# SALO_CONTROLLER_PCB.net
KiCad netlist of a schematic drawn in Altium Designer
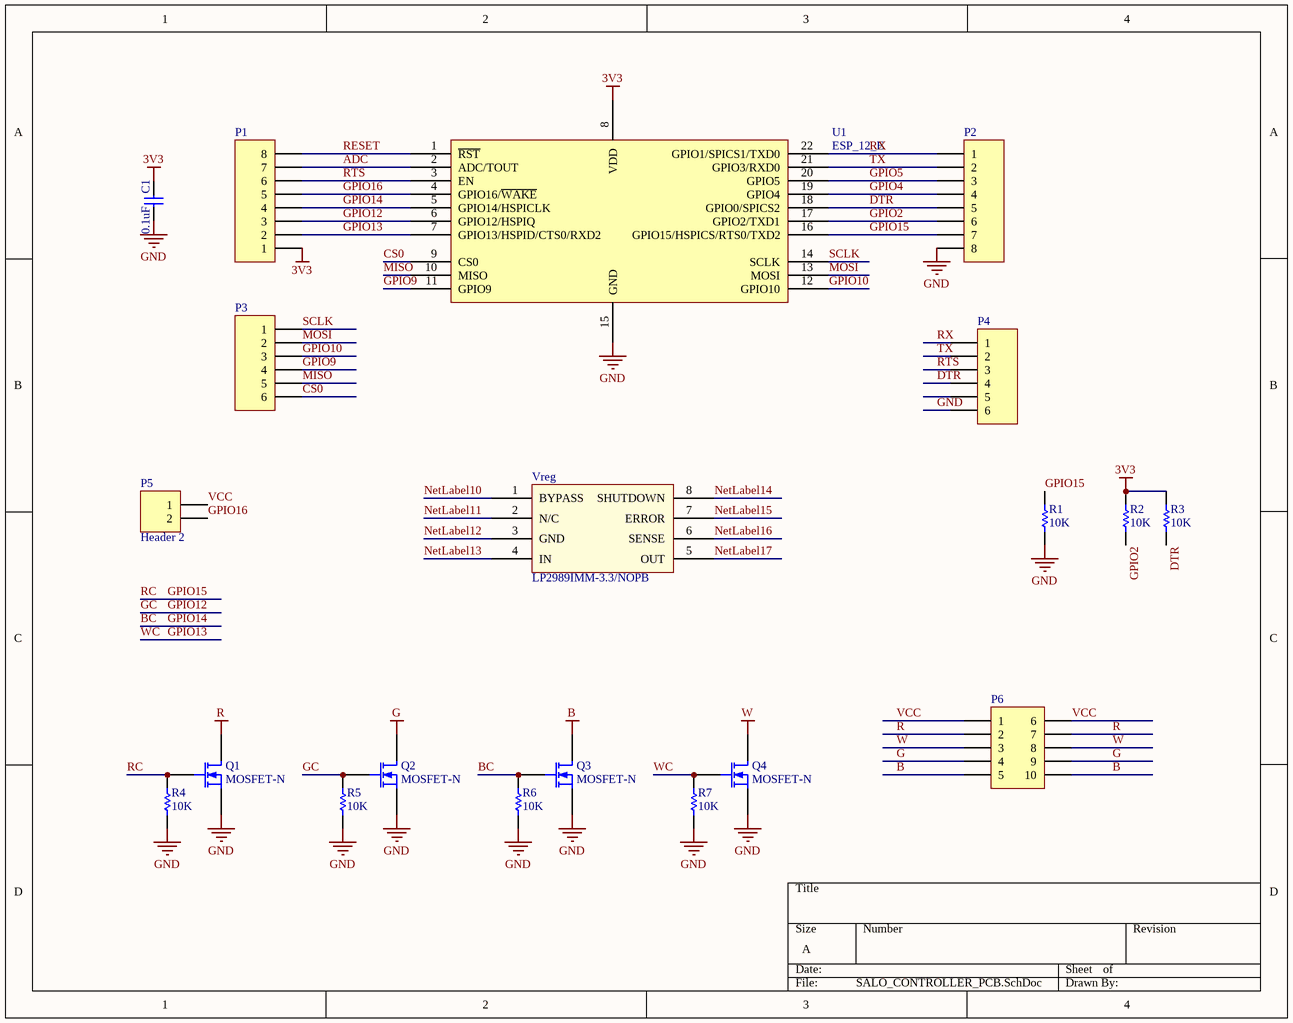
[diagram p0: SALO_CONTROLLER_PCB.SchDoc]

(export (version "E")
  (design (tool "Eeschema 10.0.6"))
  (components
    (comp (ref "C1")
      (value "0.1uF")
      (footprint "CAPC1608X06L")
      (description "Capacitor, X5R, ±10%")
      (fields (field (name "PART NUMBER") "C0603-4µ7") (field (name "PUBLISHER") "Nordic Semiconductor"))
      (libsource (lib "daniel_library") (part "CAP_0603"))
    )
    (comp (ref "P1")
      (value "Header 8")
      (footprint "HDR1X8")
      (description "Header, 8-Pin")
      (fields (field (name "PUBLISHER") "Altium Limited"))
      (libsource (lib "") (part "Header 8_1"))
    )
    (comp (ref "P2")
      (value "Header 8")
      (footprint "HDR1X8")
      (description "Header, 8-Pin")
      (fields (field (name "PUBLISHER") "Altium Limited"))
      (libsource (lib "Miscellaneous Connectors") (part "Header 8"))
    )
    (comp (ref "P3")
      (value "Header 6")
      (footprint "HDR1X6")
      (description "Header, 6-Pin")
      (fields (field (name "PUBLISHER") "Altium Limited"))
      (libsource (lib "") (part "Header 6_1"))
    )
    (comp (ref "P4")
      (value "Header 6")
      (footprint "HDR1X6")
      (description "Header, 6-Pin")
      (fields (field (name "PUBLISHER") "Altium Limited"))
      (libsource (lib "Miscellaneous Connectors") (part "Header 6"))
    )
    (comp (ref "P5")
      (value "Header 2")
      (footprint "HDR1X2")
      (description "Header, 2-Pin")
      (fields (field (name "PUBLISHER") "Altium Limited"))
      (libsource (lib "Miscellaneous Connectors") (part "Header 2"))
    )
    (comp (ref "P6")
      (value "Header 5X2A")
      (footprint "HDR2X5_CEN")
      (description "Header, 5-Pin, Dual row")
      (fields (field (name "PUBLISHER") "Altium Limited"))
      (libsource (lib "Miscellaneous Connectors") (part "Header 5X2A"))
    )
    (comp (ref "Q1")
      (value "MOSFET-N")
      (footprint "DPAK")
      (description "N-Channel MOSFET")
      (libsource (lib "daniel_library") (part "MOSFET-N"))
    )
    (comp (ref "Q2")
      (value "MOSFET-N")
      (footprint "DPAK")
      (description "N-Channel MOSFET")
      (libsource (lib "daniel_library") (part "MOSFET-N"))
    )
    (comp (ref "Q3")
      (value "MOSFET-N")
      (footprint "DPAK")
      (description "N-Channel MOSFET")
      (libsource (lib "daniel_library") (part "MOSFET-N"))
    )
    (comp (ref "Q4")
      (value "MOSFET-N")
      (footprint "DPAK")
      (description "N-Channel MOSFET")
      (libsource (lib "daniel_library") (part "MOSFET-N"))
    )
    (comp (ref "R1")
      (value "10K")
      (footprint "R0805")
      (description "Resistor")
      (fields (field (name "Comment") "Res1") (field (name "PUBLISHER") "Altium Limited"))
      (libsource (lib "Miscellaneous Devices") (part "Res1"))
    )
    (comp (ref "R2")
      (value "10K")
      (footprint "R0805")
      (description "Resistor")
      (fields (field (name "Comment") "Res1") (field (name "PUBLISHER") "Altium Limited"))
      (libsource (lib "Miscellaneous Devices") (part "Res1"))
    )
    (comp (ref "R3")
      (value "10K")
      (footprint "R0805")
      (description "Resistor")
      (fields (field (name "Comment") "Res1") (field (name "PUBLISHER") "Altium Limited"))
      (libsource (lib "Miscellaneous Devices") (part "Res1"))
    )
    (comp (ref "R4")
      (value "10K")
      (footprint "R0805")
      (description "Resistor")
      (fields (field (name "Comment") "Res1") (field (name "PUBLISHER") "Altium Limited"))
      (libsource (lib "Miscellaneous Devices") (part "Res1"))
    )
    (comp (ref "R5")
      (value "10K")
      (footprint "R0805")
      (description "Resistor")
      (fields (field (name "Comment") "Res1") (field (name "PUBLISHER") "Altium Limited"))
      (libsource (lib "Miscellaneous Devices") (part "Res1"))
    )
    (comp (ref "R6")
      (value "10K")
      (footprint "R0805")
      (description "Resistor")
      (fields (field (name "Comment") "Res1") (field (name "PUBLISHER") "Altium Limited"))
      (libsource (lib "Miscellaneous Devices") (part "Res1"))
    )
    (comp (ref "R7")
      (value "10K")
      (footprint "R0805")
      (description "Resistor")
      (fields (field (name "Comment") "Res1") (field (name "PUBLISHER") "Altium Limited"))
      (libsource (lib "Miscellaneous Devices") (part "Res1"))
    )
    (comp (ref "U1")
      (value "ESP_12_E")
      (footprint "ESP_12_E")
      (description "ESP-12 Wi-Fi Module by AI-Thinker")
      (libsource (lib "daniel_library") (part "ESP_12_E"))
    )
    (comp (ref "Vreg")
      (value "LP2989IMM-3.3/NOPB")
      (footprint "MSOP-8")
      (description "3.3Vout 500mA Voltage Regulator")
      (libsource (lib "daniel_library") (part "LP2989IMM-3.3/NOPB"))
    )
  )
  (nets
    (net (code "1") (name "/ADC") (class "Default")
      (node (ref "P1") (pin "7") (pinfunction "7_7") (pintype "passive"))
      (node (ref "U1") (pin "2") (pinfunction "ADC/TOUT_2") (pintype "passive"))
    )
    (net (code "2") (name "/BC") (class "Default")
      (node (ref "P1") (pin "4") (pinfunction "4_4") (pintype "passive"))
      (node (ref "Q3") (pin "2") (pinfunction "G_2") (pintype "passive"))
      (node (ref "R6") (pin "2") (pinfunction "2_2") (pintype "passive"))
      (node (ref "U1") (pin "5") (pinfunction "GPIO14/HSPICLK_5") (pintype "passive"))
    )
    (net (code "3") (name "/CS0") (class "Default")
      (node (ref "P3") (pin "6") (pinfunction "6_6") (pintype "passive"))
      (node (ref "U1") (pin "9") (pinfunction "CS0_9") (pintype "passive"))
    )
    (net (code "4") (name "/DTR") (class "Default")
      (node (ref "P2") (pin "5") (pinfunction "5_5") (pintype "passive"))
      (node (ref "P4") (pin "4") (pinfunction "4_4") (pintype "passive"))
      (node (ref "R3") (pin "1") (pinfunction "1_1") (pintype "passive"))
      (node (ref "U1") (pin "18") (pinfunction "GPIO0/SPICS2_18") (pintype "passive"))
    )
    (net (code "5") (name "/GC") (class "Default")
      (node (ref "P1") (pin "3") (pinfunction "3_3") (pintype "passive"))
      (node (ref "Q2") (pin "2") (pinfunction "G_2") (pintype "passive"))
      (node (ref "R5") (pin "2") (pinfunction "2_2") (pintype "passive"))
      (node (ref "U1") (pin "6") (pinfunction "GPIO12/HSPIQ_6") (pintype "passive"))
    )
    (net (code "6") (name "/GPIO2") (class "Default")
      (node (ref "P2") (pin "6") (pinfunction "6_6") (pintype "passive"))
      (node (ref "R2") (pin "1") (pinfunction "1_1") (pintype "passive"))
      (node (ref "U1") (pin "17") (pinfunction "GPIO2/TXD1_17") (pintype "passive"))
    )
    (net (code "7") (name "/GPIO4") (class "Default")
      (node (ref "P2") (pin "4") (pinfunction "4_4") (pintype "passive"))
      (node (ref "U1") (pin "19") (pinfunction "GPIO4_19") (pintype "passive"))
    )
    (net (code "8") (name "/GPIO5") (class "Default")
      (node (ref "P2") (pin "3") (pinfunction "3_3") (pintype "passive"))
      (node (ref "U1") (pin "20") (pinfunction "GPIO5_20") (pintype "passive"))
    )
    (net (code "9") (name "/GPIO9") (class "Default")
      (node (ref "P3") (pin "4") (pinfunction "4_4") (pintype "passive"))
      (node (ref "U1") (pin "11") (pinfunction "GPIO9_11") (pintype "passive"))
    )
    (net (code "10") (name "/GPIO10") (class "Default")
      (node (ref "P3") (pin "3") (pinfunction "3_3") (pintype "passive"))
      (node (ref "U1") (pin "12") (pinfunction "GPIO10_12") (pintype "passive"))
    )
    (net (code "11") (name "/GPIO13") (class "Default")
      (node (ref "P1") (pin "2") (pinfunction "2_2") (pintype "passive"))
      (node (ref "Q4") (pin "2") (pinfunction "G_2") (pintype "passive"))
      (node (ref "R7") (pin "2") (pinfunction "2_2") (pintype "passive"))
      (node (ref "U1") (pin "7") (pinfunction "GPIO13/HSPID/CTS0/RXD2_7") (pintype "passive"))
    )
    (net (code "12") (name "/GPIO15") (class "Default")
      (node (ref "P2") (pin "7") (pinfunction "7_7") (pintype "passive"))
      (node (ref "Q1") (pin "2") (pinfunction "G_2") (pintype "passive"))
      (node (ref "R1") (pin "2") (pinfunction "2_2") (pintype "passive"))
      (node (ref "R4") (pin "2") (pinfunction "2_2") (pintype "passive"))
      (node (ref "U1") (pin "16") (pinfunction "GPIO15/HSPICS/RTS0/TXD2_16") (pintype "passive"))
    )
    (net (code "13") (name "/GPIO16") (class "Default")
      (node (ref "P1") (pin "5") (pinfunction "5_5") (pintype "passive"))
      (node (ref "P5") (pin "2") (pinfunction "2_2") (pintype "passive"))
      (node (ref "U1") (pin "4") (pinfunction "GPIO16/~{WAKE}_4") (pintype "passive"))
    )
    (net (code "14") (name "/MISO") (class "Default")
      (node (ref "P3") (pin "5") (pinfunction "5_5") (pintype "passive"))
      (node (ref "U1") (pin "10") (pinfunction "MISO_10") (pintype "passive"))
    )
    (net (code "15") (name "/MOSI") (class "Default")
      (node (ref "P3") (pin "2") (pinfunction "2_2") (pintype "passive"))
      (node (ref "U1") (pin "13") (pinfunction "MOSI_13") (pintype "passive"))
    )
    (net (code "16") (name "/NetLabel10") (class "Default")
      (node (ref "Vreg") (pin "1") (pinfunction "BYPASS_1") (pintype "passive"))
    )
    (net (code "17") (name "/NetLabel11") (class "Default")
      (node (ref "Vreg") (pin "2") (pinfunction "N/C_2") (pintype "passive"))
    )
    (net (code "18") (name "/NetLabel12") (class "Default")
      (node (ref "Vreg") (pin "3") (pinfunction "GND_3") (pintype "passive"))
    )
    (net (code "19") (name "/NetLabel13") (class "Default")
      (node (ref "Vreg") (pin "4") (pinfunction "IN_4") (pintype "passive"))
    )
    (net (code "20") (name "/NetLabel14") (class "Default")
      (node (ref "Vreg") (pin "8") (pinfunction "SHUTDOWN_8") (pintype "passive"))
    )
    (net (code "21") (name "/NetLabel15") (class "Default")
      (node (ref "Vreg") (pin "7") (pinfunction "ERROR_7") (pintype "passive"))
    )
    (net (code "22") (name "/NetLabel16") (class "Default")
      (node (ref "Vreg") (pin "6") (pinfunction "SENSE_6") (pintype "passive"))
    )
    (net (code "23") (name "/NetLabel17") (class "Default")
      (node (ref "Vreg") (pin "5") (pinfunction "OUT_5") (pintype "passive"))
    )
    (net (code "24") (name "/RESET") (class "Default")
      (node (ref "P1") (pin "8") (pinfunction "8_8") (pintype "passive"))
      (node (ref "U1") (pin "1") (pinfunction "~{RST}_1") (pintype "passive"))
    )
    (net (code "25") (name "/RTS") (class "Default")
      (node (ref "P1") (pin "6") (pinfunction "6_6") (pintype "passive"))
      (node (ref "P4") (pin "3") (pinfunction "3_3") (pintype "passive"))
      (node (ref "U1") (pin "3") (pinfunction "EN_3") (pintype "passive"))
    )
    (net (code "26") (name "/RX") (class "Default")
      (node (ref "P2") (pin "1") (pinfunction "1_1") (pintype "passive"))
      (node (ref "P4") (pin "1") (pinfunction "1_1") (pintype "passive"))
      (node (ref "U1") (pin "22") (pinfunction "GPIO1/SPICS1/TXD0_22") (pintype "passive"))
    )
    (net (code "27") (name "/SCLK") (class "Default")
      (node (ref "P3") (pin "1") (pinfunction "1_1") (pintype "passive"))
      (node (ref "U1") (pin "14") (pinfunction "SCLK_14") (pintype "passive"))
    )
    (net (code "28") (name "/TX") (class "Default")
      (node (ref "P2") (pin "2") (pinfunction "2_2") (pintype "passive"))
      (node (ref "P4") (pin "2") (pinfunction "2_2") (pintype "passive"))
      (node (ref "U1") (pin "21") (pinfunction "GPIO3/RXD0_21") (pintype "passive"))
    )
    (net (code "29") (name "/VCC") (class "Default")
      (node (ref "P5") (pin "1") (pinfunction "1_1") (pintype "passive"))
      (node (ref "P6") (pin "1") (pinfunction "1_1") (pintype "passive"))
      (node (ref "P6") (pin "6") (pinfunction "6_6") (pintype "passive"))
    )
    (net (code "30") (name "3V3") (class "Default")
      (node (ref "C1") (pin "2") (pinfunction "2_2") (pintype "passive"))
      (node (ref "P1") (pin "1") (pinfunction "1_1") (pintype "passive"))
      (node (ref "R2") (pin "2") (pinfunction "2_2") (pintype "passive"))
      (node (ref "R3") (pin "2") (pinfunction "2_2") (pintype "passive"))
      (node (ref "U1") (pin "8") (pinfunction "VDD_8") (pintype "passive"))
    )
    (net (code "31") (name "B") (class "Default")
      (node (ref "P6") (pin "10") (pinfunction "10_10") (pintype "passive"))
      (node (ref "P6") (pin "5") (pinfunction "5_5") (pintype "passive"))
      (node (ref "Q3") (pin "1") (pinfunction "D_1") (pintype "passive"))
    )
    (net (code "32") (name "G") (class "Default")
      (node (ref "P6") (pin "4") (pinfunction "4_4") (pintype "passive"))
      (node (ref "P6") (pin "9") (pinfunction "9_9") (pintype "passive"))
      (node (ref "Q2") (pin "1") (pinfunction "D_1") (pintype "passive"))
    )
    (net (code "33") (name "GND") (class "Default")
      (node (ref "C1") (pin "1") (pinfunction "1_1") (pintype "passive"))
      (node (ref "P2") (pin "8") (pinfunction "8_8") (pintype "passive"))
      (node (ref "P4") (pin "6") (pinfunction "6_6") (pintype "passive"))
      (node (ref "Q1") (pin "3") (pinfunction "S_3") (pintype "passive"))
      (node (ref "Q2") (pin "3") (pinfunction "S_3") (pintype "passive"))
      (node (ref "Q3") (pin "3") (pinfunction "S_3") (pintype "passive"))
      (node (ref "Q4") (pin "3") (pinfunction "S_3") (pintype "passive"))
      (node (ref "R1") (pin "1") (pinfunction "1_1") (pintype "passive"))
      (node (ref "R4") (pin "1") (pinfunction "1_1") (pintype "passive"))
      (node (ref "R5") (pin "1") (pinfunction "1_1") (pintype "passive"))
      (node (ref "R6") (pin "1") (pinfunction "1_1") (pintype "passive"))
      (node (ref "R7") (pin "1") (pinfunction "1_1") (pintype "passive"))
      (node (ref "U1") (pin "15") (pinfunction "GND_15") (pintype "passive"))
    )
    (net (code "34") (name "R") (class "Default")
      (node (ref "P6") (pin "2") (pinfunction "2_2") (pintype "passive"))
      (node (ref "P6") (pin "7") (pinfunction "7_7") (pintype "passive"))
      (node (ref "Q1") (pin "1") (pinfunction "D_1") (pintype "passive"))
    )
    (net (code "35") (name "W") (class "Default")
      (node (ref "P6") (pin "3") (pinfunction "3_3") (pintype "passive"))
      (node (ref "P6") (pin "8") (pinfunction "8_8") (pintype "passive"))
      (node (ref "Q4") (pin "1") (pinfunction "D_1") (pintype "passive"))
    )
    (net (code "36") (name "unconnected-(P4-Pad5)") (class "Default")
      (node (ref "P4") (pin "5") (pinfunction "5_5") (pintype "passive"))
    )
  )
)
